# NVME.net
KiCad netlist of a schematic drawn in Altium Designer
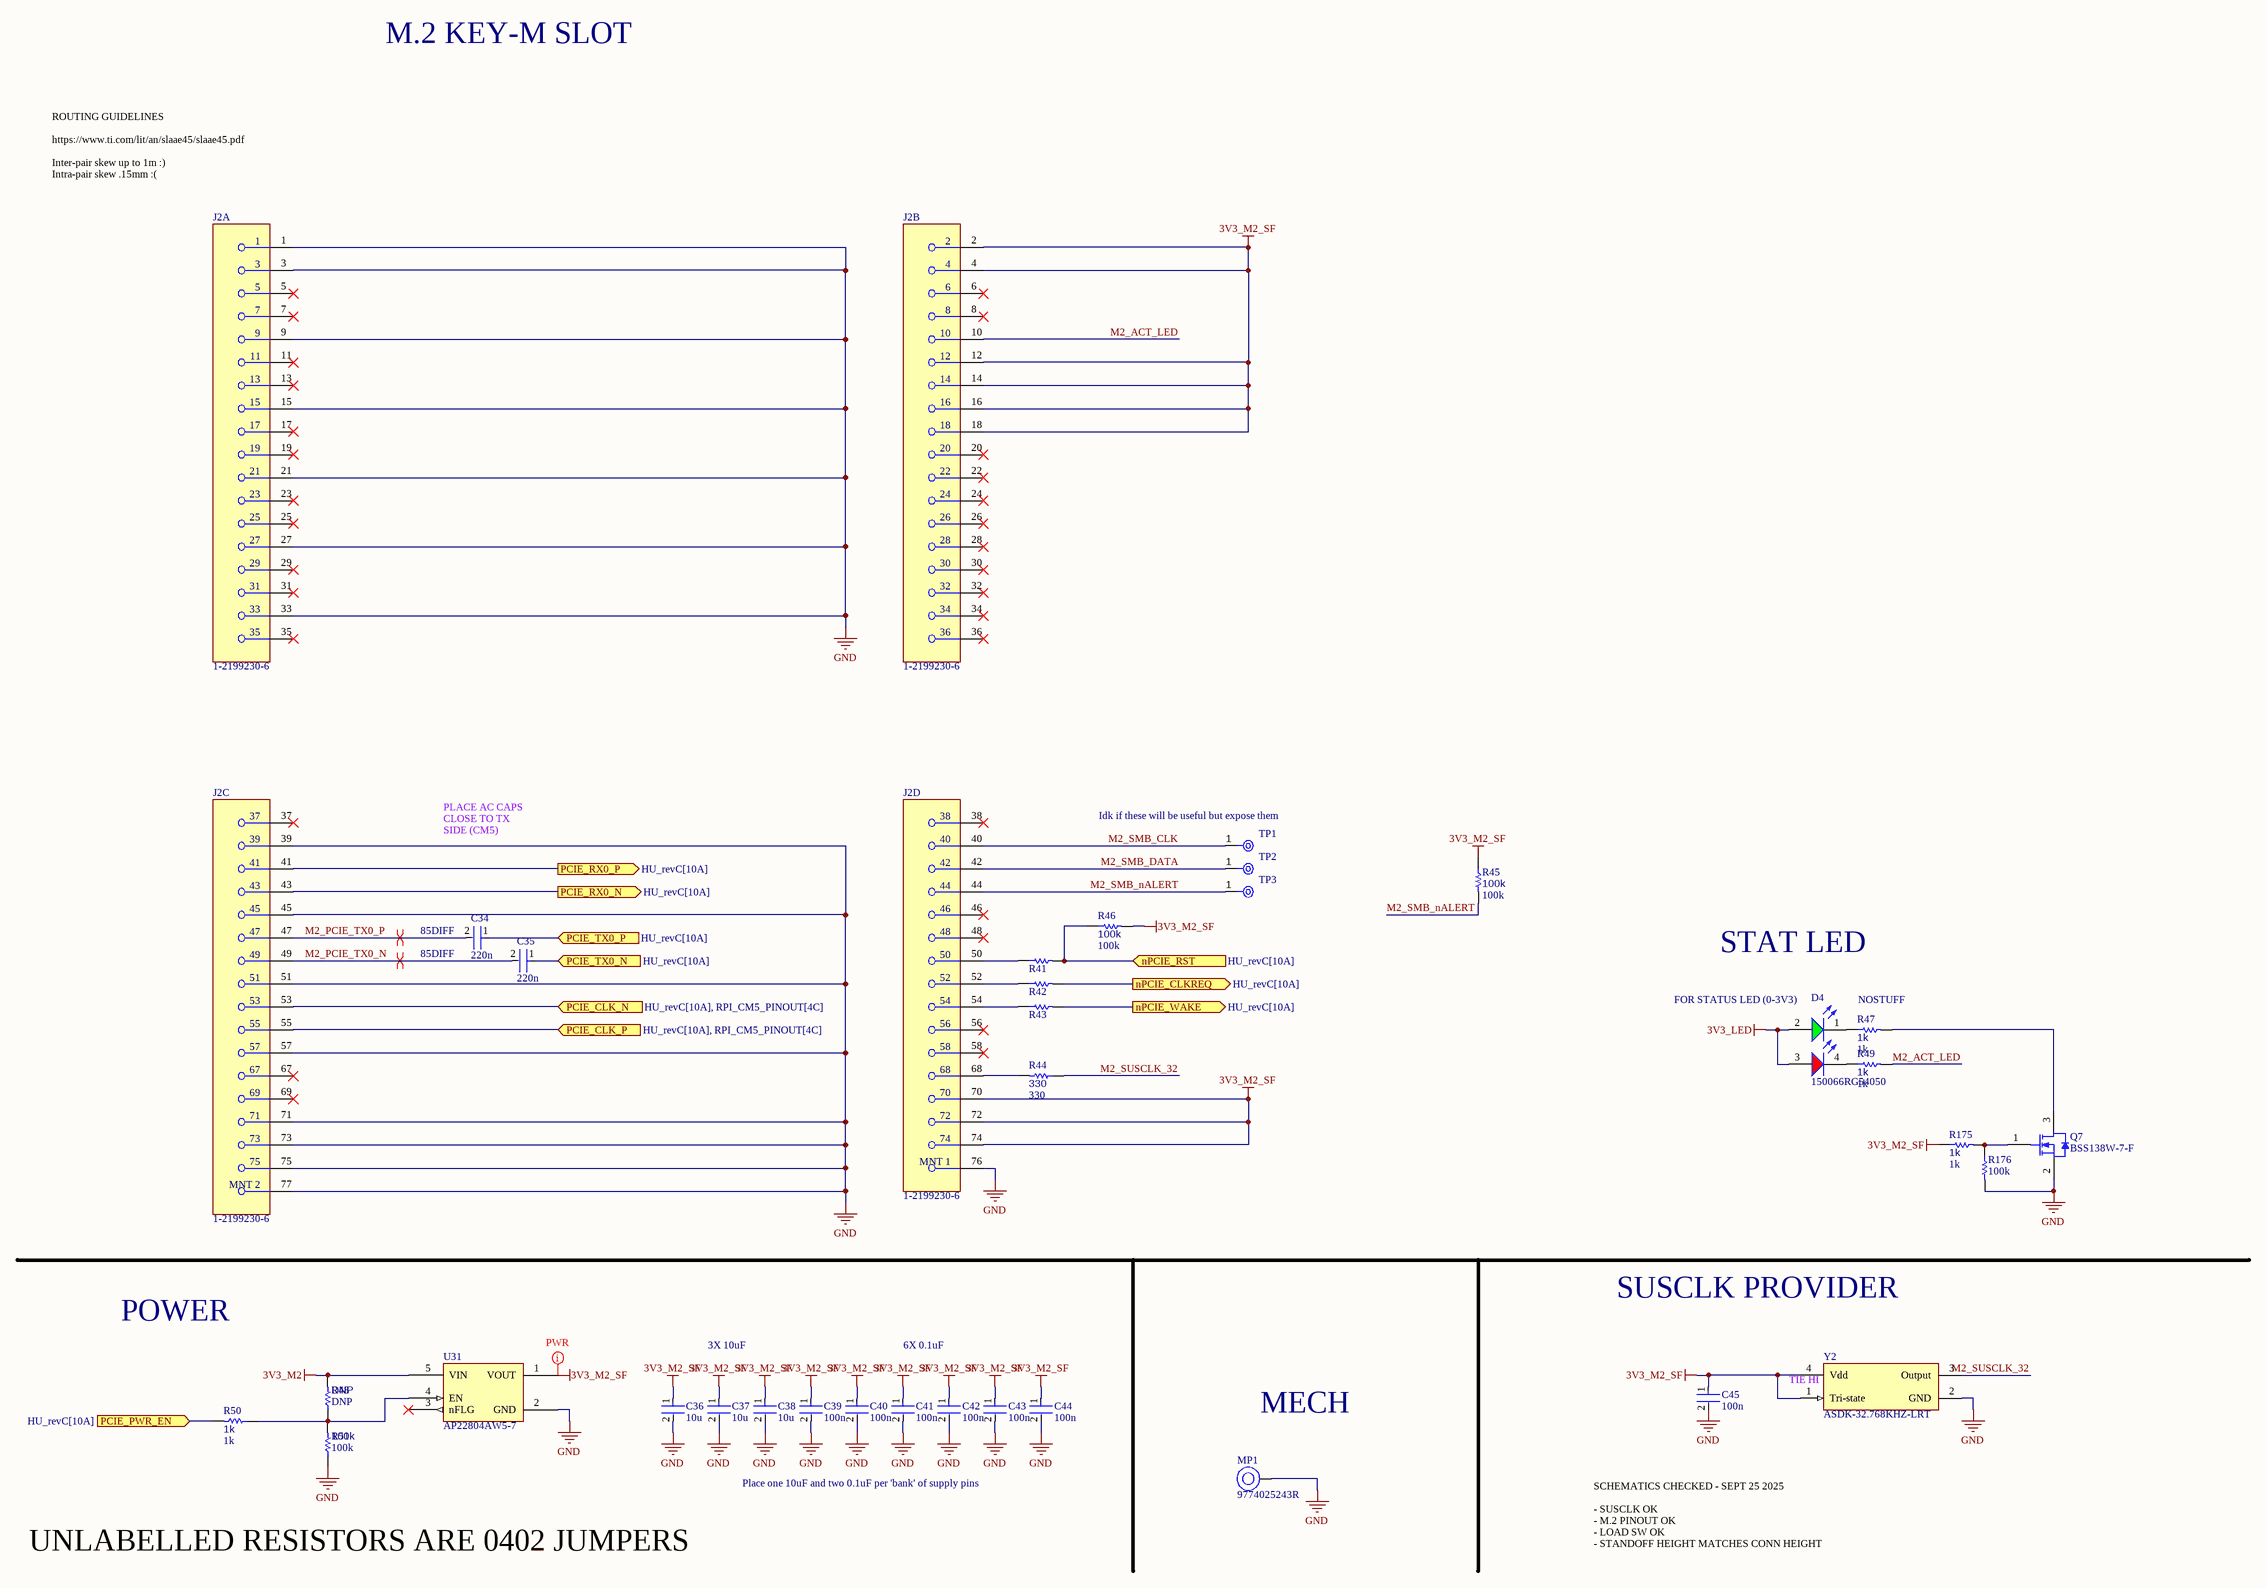
[diagram p0: NVME.SchDoc]

(export (version "E")
  (design (tool "Eeschema 10.0.6"))
  (components
    (comp (ref "C34")
      (value "220n")
      (footprint "FP-0402-L_1_0_0_05-W_0_5-IPC_A")
      (description "LARGE PADS, 0402 CAP, CHANGE COMMENT TO MATCH REAL P/N")
      (libsource (lib "Space Concordia") (part "b4654b650e69147ec39a6b967a45e02"))
    )
    (comp (ref "C35")
      (value "220n")
      (footprint "FP-0402-L_1_0_0_05-W_0_5-IPC_A")
      (description "LARGE PADS, 0402 CAP, CHANGE COMMENT TO MATCH REAL P/N")
      (libsource (lib "Space Concordia") (part "b4654b650e69147ec39a6b967a45e02"))
    )
    (comp (ref "C36")
      (value "10u")
      (footprint "FP-0402-L_1_0_0_05-W_0_5-IPC_A")
      (description "LARGE PADS, 0402 CAP, CHANGE COMMENT TO MATCH REAL P/N")
      (libsource (lib "Space Concordia") (part "b4654b650e69147ec39a6b967a45e02"))
    )
    (comp (ref "C37")
      (value "10u")
      (footprint "FP-0402-L_1_0_0_05-W_0_5-IPC_A")
      (description "LARGE PADS, 0402 CAP, CHANGE COMMENT TO MATCH REAL P/N")
      (libsource (lib "Space Concordia") (part "b4654b650e69147ec39a6b967a45e02"))
    )
    (comp (ref "C38")
      (value "10u")
      (footprint "FP-0402-L_1_0_0_05-W_0_5-IPC_A")
      (description "LARGE PADS, 0402 CAP, CHANGE COMMENT TO MATCH REAL P/N")
      (libsource (lib "Space Concordia") (part "b4654b650e69147ec39a6b967a45e02"))
    )
    (comp (ref "C39")
      (value "100n")
      (footprint "FP-0402-L_1_0_0_05-W_0_5-IPC_A")
      (description "LARGE PADS, 0402 CAP, CHANGE COMMENT TO MATCH REAL P/N")
      (libsource (lib "Space Concordia") (part "b4654b650e69147ec39a6b967a45e02"))
    )
    (comp (ref "C40")
      (value "100n")
      (footprint "FP-0402-L_1_0_0_05-W_0_5-IPC_A")
      (description "LARGE PADS, 0402 CAP, CHANGE COMMENT TO MATCH REAL P/N")
      (libsource (lib "Space Concordia") (part "b4654b650e69147ec39a6b967a45e02"))
    )
    (comp (ref "C41")
      (value "100n")
      (footprint "FP-0402-L_1_0_0_05-W_0_5-IPC_A")
      (description "LARGE PADS, 0402 CAP, CHANGE COMMENT TO MATCH REAL P/N")
      (libsource (lib "Space Concordia") (part "b4654b650e69147ec39a6b967a45e02"))
    )
    (comp (ref "C42")
      (value "100n")
      (footprint "FP-0402-L_1_0_0_05-W_0_5-IPC_A")
      (description "LARGE PADS, 0402 CAP, CHANGE COMMENT TO MATCH REAL P/N")
      (libsource (lib "Space Concordia") (part "b4654b650e69147ec39a6b967a45e02"))
    )
    (comp (ref "C43")
      (value "100n")
      (footprint "FP-0402-L_1_0_0_05-W_0_5-IPC_A")
      (description "LARGE PADS, 0402 CAP, CHANGE COMMENT TO MATCH REAL P/N")
      (libsource (lib "Space Concordia") (part "b4654b650e69147ec39a6b967a45e02"))
    )
    (comp (ref "C44")
      (value "100n")
      (footprint "FP-0402-L_1_0_0_05-W_0_5-IPC_A")
      (description "LARGE PADS, 0402 CAP, CHANGE COMMENT TO MATCH REAL P/N")
      (libsource (lib "Space Concordia") (part "b4654b650e69147ec39a6b967a45e02"))
    )
    (comp (ref "C45")
      (value "100n")
      (footprint "FP-0402-L_1_0_0_05-W_0_5-IPC_A")
      (description "LARGE PADS, 0402 CAP, CHANGE COMMENT TO MATCH REAL P/N")
      (libsource (lib "Space Concordia") (part "b4654b650e69147ec39a6b967a45e02"))
    )
    (comp (ref "D4")
      (value "150066RG54050")
      (footprint "WL-SBCD_0606")
      (description "Led, Red/Grn, 180Mcd/230Mcd, 624Nm/525Nm Rohs Compliant: Yes")
      (fields (field (name "SOURCE") "rgled.SchLib"))
      (libsource (lib "Space Concordia") (part "CMP-004-00034-2"))
    )
    (comp (ref "J2")
      (value "1-2199230-6")
      (footprint "FP-1-2199230-6-MFG")
      (description "CONN EDGE DUAL FMALE 67POS 0.020")
      (fields
        (field (name "MANUFACTURER") "TE")
        (field (name "OCTOPART") "https://octopart.com/1-2199230-6-te+connectivity-34969376")
      )
      (libsource (lib "Altium Content Vault") (part "bdc5cd39fb5e3adfc3cf7d042564072"))
    )
    (comp (ref "MP1")
      (value "9774025243R")
      (footprint "9774025243")
      (description "9774025243R Spacer Material: Steel, Tin-Plated Mounting: SMT Series: WA-SMST Thread D: M2")
      (libsource (lib "Altium Content Vault") (part "Spacer"))
    )
    (comp (ref "Q7")
      (value "BSS138W-7-F")
      (footprint "DIOD-SOT323-3_V")
      (fields (field (name "MANUFACTURER") "DiodesIncorporated"))
      (libsource (lib "Altium Content Vault") (part "NEMOS-GSD-3"))
    )
    (comp (ref "R41")
      (value "0402 JUMPER")
      (footprint "RESC1005X40X25ML05T05")
      (description "READ THE NAME")
      (libsource (lib "Space Concordia") (part "CMP-009-00206-2"))
    )
    (comp (ref "R42")
      (value "0402 JUMPER")
      (footprint "RESC1005X40X25ML05T05")
      (description "READ THE NAME")
      (libsource (lib "Space Concordia") (part "CMP-009-00206-2"))
    )
    (comp (ref "R43")
      (value "0402 JUMPER")
      (footprint "RESC1005X40X25ML05T05")
      (description "READ THE NAME")
      (libsource (lib "Space Concordia") (part "CMP-009-00206-2"))
    )
    (comp (ref "R44")
      (value "330")
      (footprint "R0603B")
      (description "Resistor")
      (fields (field (name "ALTIUM_VALUE") "330"))
      (libsource (lib "Space Concordia") (part "Resistor"))
    )
    (comp (ref "R45")
      (value "100k")
      (footprint "R0603B")
      (description "Resistor")
      (fields (field (name "ALTIUM_VALUE") "100k"))
      (libsource (lib "Space Concordia") (part "Resistor"))
    )
    (comp (ref "R46")
      (value "100k")
      (footprint "R0603B")
      (description "Resistor")
      (fields (field (name "ALTIUM_VALUE") "100k"))
      (libsource (lib "Space Concordia") (part "Resistor"))
    )
    (comp (ref "R47")
      (value "1k")
      (footprint "R0603B")
      (description "Resistor")
      (fields (field (name "ALTIUM_VALUE") "1k"))
      (libsource (lib "Space Concordia") (part "Resistor"))
    )
    (comp (ref "R48")
      (value "DNP")
      (footprint "R0603B")
      (description "Resistor")
      (fields (field (name "ALTIUM_VALUE") "DNP"))
      (libsource (lib "Space Concordia") (part "Resistor"))
    )
    (comp (ref "R49")
      (value "1k")
      (footprint "R0603B")
      (description "Resistor")
      (fields (field (name "ALTIUM_VALUE") "1k"))
      (libsource (lib "Space Concordia") (part "Resistor"))
    )
    (comp (ref "R50")
      (value "1k")
      (footprint "R0603B")
      (description "Resistor")
      (fields (field (name "ALTIUM_VALUE") "1k"))
      (libsource (lib "Space Concordia") (part "Resistor"))
    )
    (comp (ref "R51")
      (value "100k")
      (footprint "R0603B")
      (description "Resistor")
      (fields (field (name "ALTIUM_VALUE") "100k"))
      (libsource (lib "Space Concordia") (part "Resistor"))
    )
    (comp (ref "R175")
      (value "1k")
      (footprint "R0603B")
      (description "Resistor")
      (fields (field (name "ALTIUM_VALUE") "1k"))
      (libsource (lib "Space Concordia") (part "Resistor"))
    )
    (comp (ref "R176")
      (value "100k")
      (footprint "R0603B")
      (description "Resistor")
      (libsource (lib "Space Concordia") (part "Resistor"))
    )
    (comp (ref "TP1")
      (value "TPAD6R")
      (footprint "New footprint 1")
      (description "Test Point .6mm")
      (libsource (lib "Space Concordia") (part "TP"))
    )
    (comp (ref "TP2")
      (value "TPAD6R")
      (footprint "New footprint 1")
      (description "Test Point .6mm")
      (libsource (lib "Space Concordia") (part "TP"))
    )
    (comp (ref "TP3")
      (value "TPAD6R")
      (footprint "New footprint 1")
      (description "Test Point .6mm")
      (libsource (lib "Space Concordia") (part "TP"))
    )
    (comp (ref "U31")
      (value "AP22804AW5-7")
      (footprint "SOT95P285X140-5N")
      (description "SINGLE CHANNEL POWER DISTRIBUTION LOAD SWITCH, -40 to 85°C pF, RoHS")
      (libsource (lib "Space Concordia") (part "AP22804AW5-7"))
    )
    (comp (ref "Y2")
      (value "ASDK-32.768KHZ-LRT")
      (footprint "FP-ASDK-MFG")
      (description "XTAL OSC XO 32.7680KHZ CMOS SMD")
      (libsource (lib "Altium Content Vault") (part "a7425352bb6ebc83bfd0f12a23808e7"))
    )
  )
  (nets
    (net (code "1") (name "/M2_ACT_LED") (class "Default")
      (node (ref "J2") (pin "10") (pinfunction "10_10") (pintype "passive"))
      (node (ref "R49") (pin "2") (pinfunction "2_2") (pintype "passive"))
    )
    (net (code "2") (name "/M2_PCIE_TX0_N") (class "Default")
      (node (ref "C35") (pin "2") (pinfunction "2_2") (pintype "passive"))
      (node (ref "J2") (pin "49") (pinfunction "49_49") (pintype "passive"))
    )
    (net (code "3") (name "/M2_PCIE_TX0_P") (class "Default")
      (node (ref "C34") (pin "2") (pinfunction "2_2") (pintype "passive"))
      (node (ref "J2") (pin "47") (pinfunction "47_47") (pintype "passive"))
    )
    (net (code "4") (name "/M2_SMB_CLK") (class "Default")
      (node (ref "J2") (pin "40") (pinfunction "40_40") (pintype "passive"))
      (node (ref "TP1") (pin "1") (pinfunction "TP_1") (pintype "passive"))
    )
    (net (code "5") (name "/M2_SMB_DATA") (class "Default")
      (node (ref "J2") (pin "42") (pinfunction "42_42") (pintype "passive"))
      (node (ref "TP2") (pin "1") (pinfunction "TP_1") (pintype "passive"))
    )
    (net (code "6") (name "/M2_SMB_nALERT") (class "Default")
      (node (ref "J2") (pin "44") (pinfunction "44_44") (pintype "passive"))
      (node (ref "R45") (pin "2") (pinfunction "2_2") (pintype "passive"))
      (node (ref "TP3") (pin "1") (pinfunction "TP_1") (pintype "passive"))
    )
    (net (code "7") (name "/M2_SUSCLK_32") (class "Default")
      (node (ref "R44") (pin "1") (pinfunction "1_1") (pintype "passive"))
      (node (ref "Y2") (pin "3") (pinfunction "Output_3") (pintype "tri_state"))
    )
    (net (code "8") (name "/PCIE_CLK_N") (class "Default")
      (node (ref "J2") (pin "53") (pinfunction "53_53") (pintype "passive"))
    )
    (net (code "9") (name "/PCIE_CLK_P") (class "Default")
      (node (ref "J2") (pin "55") (pinfunction "55_55") (pintype "passive"))
    )
    (net (code "10") (name "/PCIE_PWR_EN") (class "Default")
      (node (ref "R50") (pin "2") (pinfunction "2_2") (pintype "passive"))
    )
    (net (code "11") (name "/PCIE_RX0_N") (class "Default")
      (node (ref "J2") (pin "43") (pinfunction "43_43") (pintype "passive"))
    )
    (net (code "12") (name "/PCIE_RX0_P") (class "Default")
      (node (ref "J2") (pin "41") (pinfunction "41_41") (pintype "passive"))
    )
    (net (code "13") (name "/PCIE_TX0_N") (class "Default")
      (node (ref "C35") (pin "1") (pinfunction "1_1") (pintype "passive"))
    )
    (net (code "14") (name "/PCIE_TX0_P") (class "Default")
      (node (ref "C34") (pin "1") (pinfunction "1_1") (pintype "passive"))
    )
    (net (code "15") (name "/nPCIE_CLKREQ") (class "Default")
      (node (ref "R42") (pin "2") (pinfunction "2_2") (pintype "passive"))
    )
    (net (code "16") (name "/nPCIE_RST") (class "Default")
      (node (ref "R41") (pin "2") (pinfunction "2_2") (pintype "passive"))
      (node (ref "R46") (pin "1") (pinfunction "1_1") (pintype "passive"))
    )
    (net (code "17") (name "/nPCIE_WAKE") (class "Default")
      (node (ref "R43") (pin "2") (pinfunction "2_2") (pintype "passive"))
    )
    (net (code "18") (name "3V3_LED") (class "Default")
      (node (ref "D4") (pin "2") (pinfunction "A_2") (pintype "passive"))
      (node (ref "D4") (pin "3") (pinfunction "A_3") (pintype "passive"))
    )
    (net (code "19") (name "3V3_M2") (class "Default")
      (node (ref "R48") (pin "2") (pinfunction "2_2") (pintype "passive"))
      (node (ref "U31") (pin "5") (pinfunction "VIN_5") (pintype "power_in"))
    )
    (net (code "20") (name "3V3_M2_SF") (class "Default")
      (node (ref "C36") (pin "1") (pinfunction "1_1") (pintype "passive"))
      (node (ref "C37") (pin "1") (pinfunction "1_1") (pintype "passive"))
      (node (ref "C38") (pin "1") (pinfunction "1_1") (pintype "passive"))
      (node (ref "C39") (pin "1") (pinfunction "1_1") (pintype "passive"))
      (node (ref "C40") (pin "1") (pinfunction "1_1") (pintype "passive"))
      (node (ref "C41") (pin "1") (pinfunction "1_1") (pintype "passive"))
      (node (ref "C42") (pin "1") (pinfunction "1_1") (pintype "passive"))
      (node (ref "C43") (pin "1") (pinfunction "1_1") (pintype "passive"))
      (node (ref "C44") (pin "1") (pinfunction "1_1") (pintype "passive"))
      (node (ref "C45") (pin "1") (pinfunction "1_1") (pintype "passive"))
      (node (ref "J2") (pin "12") (pinfunction "12_12") (pintype "passive"))
      (node (ref "J2") (pin "14") (pinfunction "14_14") (pintype "passive"))
      (node (ref "J2") (pin "16") (pinfunction "16_16") (pintype "passive"))
      (node (ref "J2") (pin "18") (pinfunction "18_18") (pintype "passive"))
      (node (ref "J2") (pin "2") (pinfunction "2_2") (pintype "passive"))
      (node (ref "J2") (pin "4") (pinfunction "4_4") (pintype "passive"))
      (node (ref "J2") (pin "70") (pinfunction "70_70") (pintype "passive"))
      (node (ref "J2") (pin "72") (pinfunction "72_72") (pintype "passive"))
      (node (ref "J2") (pin "74") (pinfunction "74_74") (pintype "passive"))
      (node (ref "R175") (pin "1") (pinfunction "1_1") (pintype "passive"))
      (node (ref "R45") (pin "1") (pinfunction "1_1") (pintype "passive"))
      (node (ref "R46") (pin "2") (pinfunction "2_2") (pintype "passive"))
      (node (ref "U31") (pin "1") (pinfunction "VOUT_1") (pintype "power_in"))
      (node (ref "Y2") (pin "1") (pinfunction "Tri-state_1") (pintype "input"))
      (node (ref "Y2") (pin "4") (pinfunction "Vdd_4") (pintype "power_in"))
    )
    (net (code "21") (name "GND") (class "Default")
      (node (ref "C36") (pin "2") (pinfunction "2_2") (pintype "passive"))
      (node (ref "C37") (pin "2") (pinfunction "2_2") (pintype "passive"))
      (node (ref "C38") (pin "2") (pinfunction "2_2") (pintype "passive"))
      (node (ref "C39") (pin "2") (pinfunction "2_2") (pintype "passive"))
      (node (ref "C40") (pin "2") (pinfunction "2_2") (pintype "passive"))
      (node (ref "C41") (pin "2") (pinfunction "2_2") (pintype "passive"))
      (node (ref "C42") (pin "2") (pinfunction "2_2") (pintype "passive"))
      (node (ref "C43") (pin "2") (pinfunction "2_2") (pintype "passive"))
      (node (ref "C44") (pin "2") (pinfunction "2_2") (pintype "passive"))
      (node (ref "C45") (pin "2") (pinfunction "2_2") (pintype "passive"))
      (node (ref "J2") (pin "1") (pinfunction "1_1") (pintype "passive"))
      (node (ref "J2") (pin "15") (pinfunction "15_15") (pintype "passive"))
      (node (ref "J2") (pin "21") (pinfunction "21_21") (pintype "passive"))
      (node (ref "J2") (pin "27") (pinfunction "27_27") (pintype "passive"))
      (node (ref "J2") (pin "3") (pinfunction "3_3") (pintype "passive"))
      (node (ref "J2") (pin "33") (pinfunction "33_33") (pintype "passive"))
      (node (ref "J2") (pin "39") (pinfunction "39_39") (pintype "passive"))
      (node (ref "J2") (pin "45") (pinfunction "45_45") (pintype "passive"))
      (node (ref "J2") (pin "51") (pinfunction "51_51") (pintype "passive"))
      (node (ref "J2") (pin "57") (pinfunction "57_57") (pintype "passive"))
      (node (ref "J2") (pin "71") (pinfunction "71_71") (pintype "passive"))
      (node (ref "J2") (pin "73") (pinfunction "73_73") (pintype "passive"))
      (node (ref "J2") (pin "75") (pinfunction "75_75") (pintype "passive"))
      (node (ref "J2") (pin "76") (pinfunction "MNT_1_76") (pintype "passive"))
      (node (ref "J2") (pin "77") (pinfunction "MNT_2_77") (pintype "passive"))
      (node (ref "J2") (pin "9") (pinfunction "9_9") (pintype "passive"))
      (node (ref "MP1") (pin "1") (pinfunction "1_1") (pintype "passive"))
      (node (ref "Q7") (pin "2") (pinfunction "S_2") (pintype "passive"))
      (node (ref "R176") (pin "2") (pinfunction "2_2") (pintype "passive"))
      (node (ref "R51") (pin "1") (pinfunction "1_1") (pintype "passive"))
      (node (ref "U31") (pin "2") (pinfunction "GND_2") (pintype "power_in"))
      (node (ref "Y2") (pin "2") (pinfunction "GND_2") (pintype "power_in"))
    )
    (net (code "22") (name "Net-(D4-K-Pad1)") (class "Default")
      (node (ref "D4") (pin "1") (pinfunction "K_1") (pintype "passive"))
      (node (ref "R47") (pin "1") (pinfunction "1_1") (pintype "passive"))
    )
    (net (code "23") (name "Net-(D4-K-Pad4)") (class "Default")
      (node (ref "D4") (pin "4") (pinfunction "K_4") (pintype "passive"))
      (node (ref "R49") (pin "1") (pinfunction "1_1") (pintype "passive"))
    )
    (net (code "24") (name "Net-(J2-Pad50)") (class "Default")
      (node (ref "J2") (pin "50") (pinfunction "50_50") (pintype "passive"))
      (node (ref "R41") (pin "1") (pinfunction "1_1") (pintype "passive"))
    )
    (net (code "25") (name "Net-(J2-Pad52)") (class "Default")
      (node (ref "J2") (pin "52") (pinfunction "52_52") (pintype "passive"))
      (node (ref "R42") (pin "1") (pinfunction "1_1") (pintype "passive"))
    )
    (net (code "26") (name "Net-(J2-Pad54)") (class "Default")
      (node (ref "J2") (pin "54") (pinfunction "54_54") (pintype "passive"))
      (node (ref "R43") (pin "1") (pinfunction "1_1") (pintype "passive"))
    )
    (net (code "27") (name "Net-(J2-Pad68)") (class "Default")
      (node (ref "J2") (pin "68") (pinfunction "68_68") (pintype "passive"))
      (node (ref "R44") (pin "2") (pinfunction "2_2") (pintype "passive"))
    )
    (net (code "28") (name "Net-(Q7-D)") (class "Default")
      (node (ref "Q7") (pin "3") (pinfunction "D_3") (pintype "passive"))
      (node (ref "R47") (pin "2") (pinfunction "2_2") (pintype "passive"))
    )
    (net (code "29") (name "Net-(Q7-G)") (class "Default")
      (node (ref "Q7") (pin "1") (pinfunction "G_1") (pintype "passive"))
      (node (ref "R175") (pin "2") (pinfunction "2_2") (pintype "passive"))
      (node (ref "R176") (pin "1") (pinfunction "1_1") (pintype "passive"))
    )
    (net (code "30") (name "Net-(U31-EN)") (class "Default")
      (node (ref "R48") (pin "1") (pinfunction "1_1") (pintype "passive"))
      (node (ref "R50") (pin "1") (pinfunction "1_1") (pintype "passive"))
      (node (ref "R51") (pin "2") (pinfunction "2_2") (pintype "passive"))
      (node (ref "U31") (pin "4") (pinfunction "EN_4") (pintype "input"))
    )
    (net (code "31") (name "unconnected-(J2-Pad5)") (class "Default")
      (node (ref "J2") (pin "5") (pinfunction "5_5") (pintype "passive+no_connect"))
    )
    (net (code "32") (name "unconnected-(J2-Pad6)") (class "Default")
      (node (ref "J2") (pin "6") (pinfunction "6_6") (pintype "passive+no_connect"))
    )
    (net (code "33") (name "unconnected-(J2-Pad7)") (class "Default")
      (node (ref "J2") (pin "7") (pinfunction "7_7") (pintype "passive+no_connect"))
    )
    (net (code "34") (name "unconnected-(J2-Pad8)") (class "Default")
      (node (ref "J2") (pin "8") (pinfunction "8_8") (pintype "passive+no_connect"))
    )
    (net (code "35") (name "unconnected-(J2-Pad11)") (class "Default")
      (node (ref "J2") (pin "11") (pinfunction "11_11") (pintype "passive+no_connect"))
    )
    (net (code "36") (name "unconnected-(J2-Pad13)") (class "Default")
      (node (ref "J2") (pin "13") (pinfunction "13_13") (pintype "passive+no_connect"))
    )
    (net (code "37") (name "unconnected-(J2-Pad17)") (class "Default")
      (node (ref "J2") (pin "17") (pinfunction "17_17") (pintype "passive+no_connect"))
    )
    (net (code "38") (name "unconnected-(J2-Pad19)") (class "Default")
      (node (ref "J2") (pin "19") (pinfunction "19_19") (pintype "passive+no_connect"))
    )
    (net (code "39") (name "unconnected-(J2-Pad20)") (class "Default")
      (node (ref "J2") (pin "20") (pinfunction "20_20") (pintype "passive+no_connect"))
    )
    (net (code "40") (name "unconnected-(J2-Pad22)") (class "Default")
      (node (ref "J2") (pin "22") (pinfunction "22_22") (pintype "passive+no_connect"))
    )
    (net (code "41") (name "unconnected-(J2-Pad23)") (class "Default")
      (node (ref "J2") (pin "23") (pinfunction "23_23") (pintype "passive+no_connect"))
    )
    (net (code "42") (name "unconnected-(J2-Pad24)") (class "Default")
      (node (ref "J2") (pin "24") (pinfunction "24_24") (pintype "passive+no_connect"))
    )
    (net (code "43") (name "unconnected-(J2-Pad25)") (class "Default")
      (node (ref "J2") (pin "25") (pinfunction "25_25") (pintype "passive+no_connect"))
    )
    (net (code "44") (name "unconnected-(J2-Pad26)") (class "Default")
      (node (ref "J2") (pin "26") (pinfunction "26_26") (pintype "passive+no_connect"))
    )
    (net (code "45") (name "unconnected-(J2-Pad28)") (class "Default")
      (node (ref "J2") (pin "28") (pinfunction "28_28") (pintype "passive+no_connect"))
    )
    (net (code "46") (name "unconnected-(J2-Pad29)") (class "Default")
      (node (ref "J2") (pin "29") (pinfunction "29_29") (pintype "passive+no_connect"))
    )
    (net (code "47") (name "unconnected-(J2-Pad30)") (class "Default")
      (node (ref "J2") (pin "30") (pinfunction "30_30") (pintype "passive+no_connect"))
    )
    (net (code "48") (name "unconnected-(J2-Pad31)") (class "Default")
      (node (ref "J2") (pin "31") (pinfunction "31_31") (pintype "passive+no_connect"))
    )
    (net (code "49") (name "unconnected-(J2-Pad32)") (class "Default")
      (node (ref "J2") (pin "32") (pinfunction "32_32") (pintype "passive+no_connect"))
    )
    (net (code "50") (name "unconnected-(J2-Pad34)") (class "Default")
      (node (ref "J2") (pin "34") (pinfunction "34_34") (pintype "passive+no_connect"))
    )
    (net (code "51") (name "unconnected-(J2-Pad35)") (class "Default")
      (node (ref "J2") (pin "35") (pinfunction "35_35") (pintype "passive+no_connect"))
    )
    (net (code "52") (name "unconnected-(J2-Pad36)") (class "Default")
      (node (ref "J2") (pin "36") (pinfunction "36_36") (pintype "passive+no_connect"))
    )
    (net (code "53") (name "unconnected-(J2-Pad37)") (class "Default")
      (node (ref "J2") (pin "37") (pinfunction "37_37") (pintype "passive+no_connect"))
    )
    (net (code "54") (name "unconnected-(J2-Pad38)") (class "Default")
      (node (ref "J2") (pin "38") (pinfunction "38_38") (pintype "passive+no_connect"))
    )
    (net (code "55") (name "unconnected-(J2-Pad46)") (class "Default")
      (node (ref "J2") (pin "46") (pinfunction "46_46") (pintype "passive+no_connect"))
    )
    (net (code "56") (name "unconnected-(J2-Pad48)") (class "Default")
      (node (ref "J2") (pin "48") (pinfunction "48_48") (pintype "passive+no_connect"))
    )
    (net (code "57") (name "unconnected-(J2-Pad56)") (class "Default")
      (node (ref "J2") (pin "56") (pinfunction "56_56") (pintype "passive+no_connect"))
    )
    (net (code "58") (name "unconnected-(J2-Pad58)") (class "Default")
      (node (ref "J2") (pin "58") (pinfunction "58_58") (pintype "passive+no_connect"))
    )
    (net (code "59") (name "unconnected-(J2-Pad67)") (class "Default")
      (node (ref "J2") (pin "67") (pinfunction "67_67") (pintype "passive+no_connect"))
    )
    (net (code "60") (name "unconnected-(J2-Pad69)") (class "Default")
      (node (ref "J2") (pin "69") (pinfunction "69_69") (pintype "passive+no_connect"))
    )
    (net (code "61") (name "unconnected-(U31-nFLG-Pad3)") (class "Default")
      (node (ref "U31") (pin "3") (pinfunction "nFLG_3") (pintype "output+no_connect"))
    )
  )
)
